# 15-OutputMultiplexing.net
KiCad netlist of a schematic drawn in Altium Designer
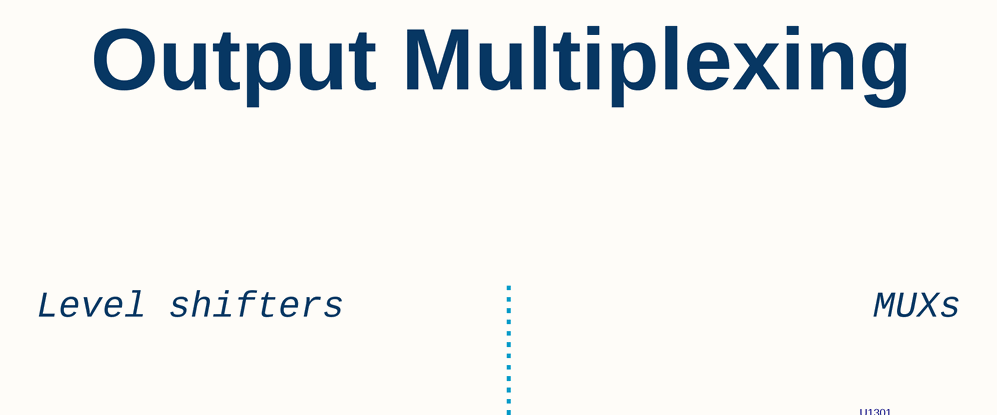
[diagram p0: 15-OutputMultiplexing.SchDoc, top left]
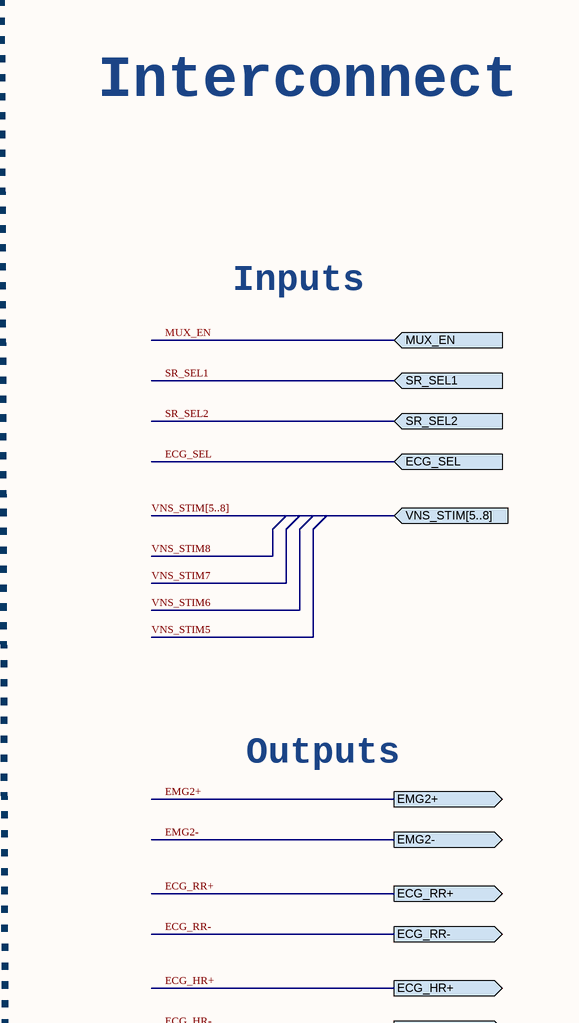
[diagram p1: 15-OutputMultiplexing.SchDoc, top right]
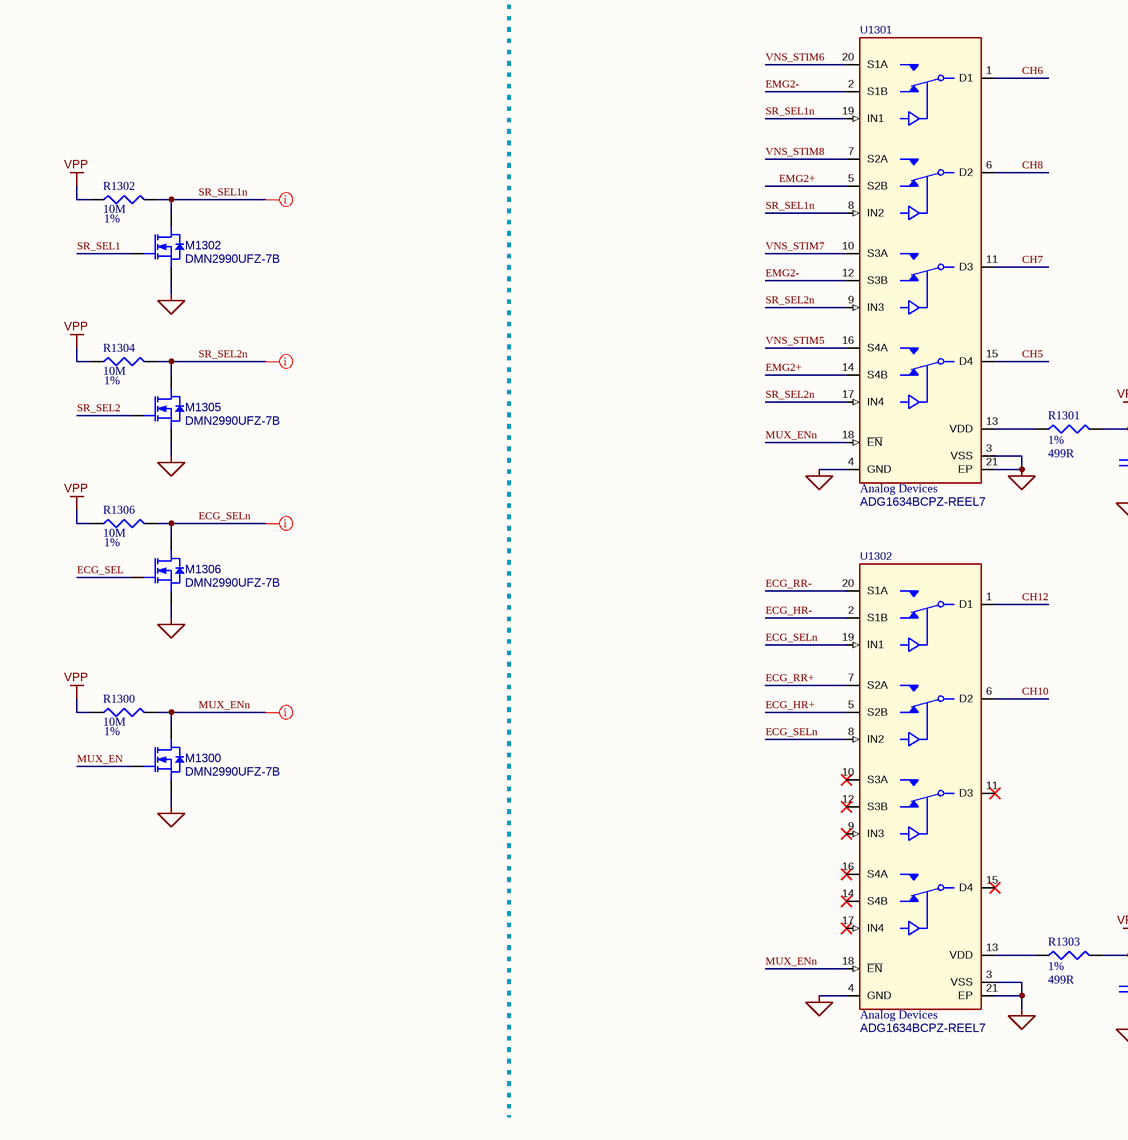
[diagram p2: 15-OutputMultiplexing.SchDoc, bottom left]
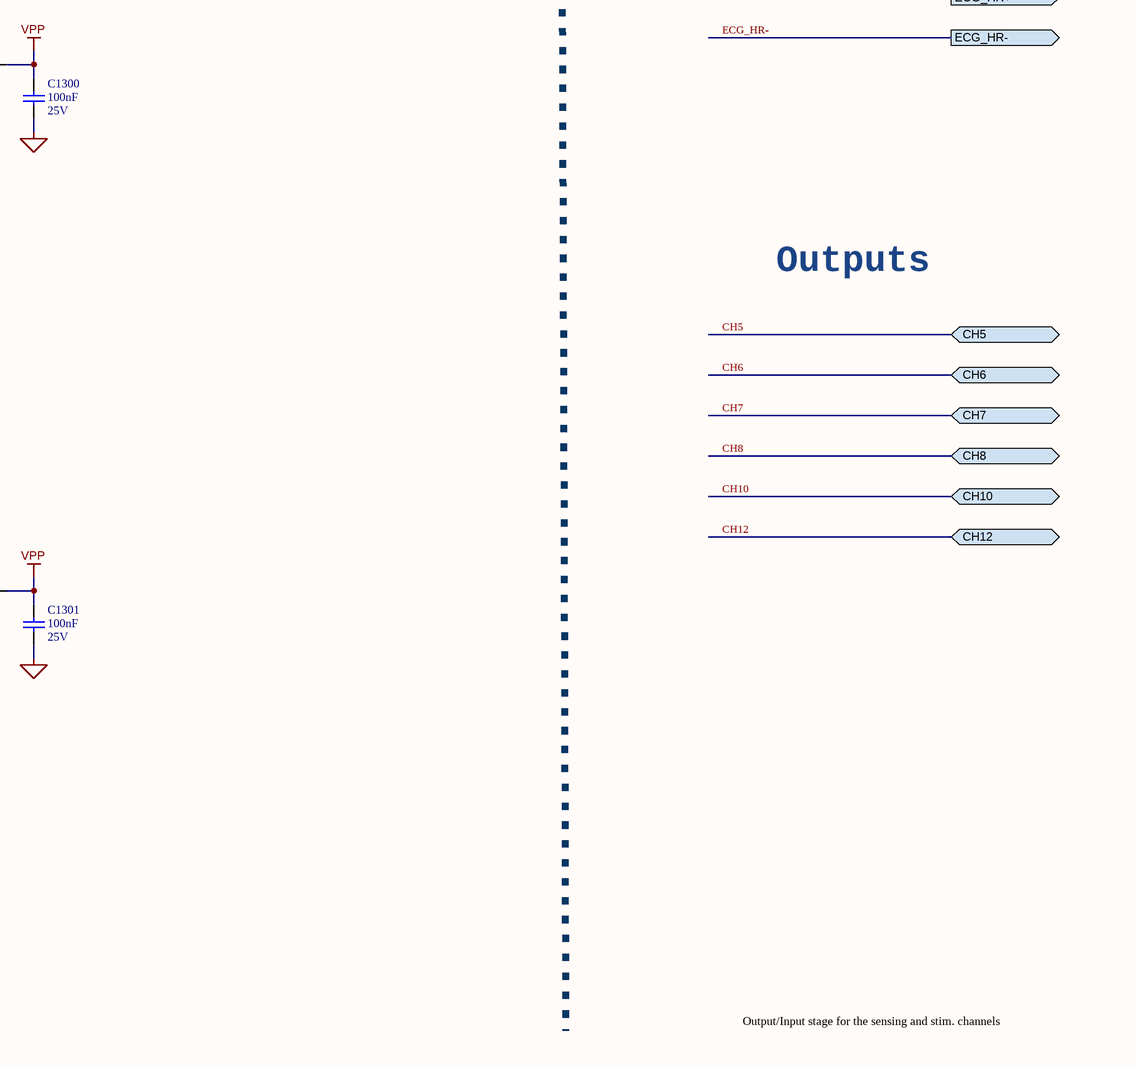
[diagram p3: 15-OutputMultiplexing.SchDoc, bottom right]

(export (version "E")
  (design (tool "Eeschema 10.0.6"))
  (components
    (comp (ref "C1300")
      (value "100nF")
      (footprint "C0201_C")
      (fields
        (field (name "MANUFACTURER") "Murata")
        (field (name "MANUFACTURER PART NUMBER") "GRM033R61E104KE14J")
        (field (name "RATED DC VOLTAGE (URDC)") "25V")
      )
      (libsource (lib "MP-LIBRARY") (part "GRM033R61E104KE14J"))
    )
    (comp (ref "C1301")
      (value "100nF")
      (footprint "C0201_C")
      (fields
        (field (name "MANUFACTURER") "Murata")
        (field (name "MANUFACTURER PART NUMBER") "GRM033R61E104KE14J")
        (field (name "RATED DC VOLTAGE (URDC)") "25V")
      )
      (libsource (lib "MP-LIBRARY") (part "GRM033R61E104KE14J"))
    )
    (comp (ref "M1300")
      (value "DMN2990UFZ-7B")
      (footprint "DIODESINC_X2-DFN0606-3")
      (description "MOSFET, N-Chan, 20V, 170mA, DFN0606")
      (fields (field (name "MANUFACTURER") "Diodes Inc"))
      (libsource (lib "MP-LIBRARY") (part "DMN2990UFZ-7B"))
    )
    (comp (ref "M1302")
      (value "DMN2990UFZ-7B")
      (footprint "DIODESINC_X2-DFN0606-3")
      (description "MOSFET, N-Chan, 20V, 170mA, DFN0606")
      (fields (field (name "MANUFACTURER") "Diodes Inc"))
      (libsource (lib "MP-LIBRARY") (part "DMN2990UFZ-7B"))
    )
    (comp (ref "M1305")
      (value "DMN2990UFZ-7B")
      (footprint "DIODESINC_X2-DFN0606-3")
      (description "MOSFET, N-Chan, 20V, 170mA, DFN0606")
      (fields (field (name "MANUFACTURER") "Diodes Inc"))
      (libsource (lib "MP-LIBRARY") (part "DMN2990UFZ-7B"))
    )
    (comp (ref "M1306")
      (value "DMN2990UFZ-7B")
      (footprint "DIODESINC_X2-DFN0606-3")
      (description "MOSFET, N-Chan, 20V, 170mA, DFN0606")
      (fields (field (name "MANUFACTURER") "Diodes Inc"))
      (libsource (lib "MP-LIBRARY") (part "DMN2990UFZ-7B"))
    )
    (comp (ref "R1300")
      (value "10M")
      (footprint "R0201_C")
      (fields
        (field (name "MANUFACTURER") "Vishay Draloric")
        (field (name "MANUFACTURER PART NUMBER") "CRCW020110M0FNED")
        (field (name "TOLERANCE") "1%")
        (field (name "POWER") "50mW")
      )
      (libsource (lib "MP-LIBRARY") (part "CRCW020110M0FNED"))
    )
    (comp (ref "R1301")
      (value "499R")
      (footprint "RES0402_REDUCED")
      (fields
        (field (name "MANUFACTURER") "Vishay Dale")
        (field (name "MANUFACTURER PART NUMBER") "CRCW0402499RFKEDHP")
        (field (name "POWER") "200mW")
        (field (name "TOLERANCE") "1%")
      )
      (libsource (lib "MP-LIBRARY") (part "CRCW0402499RFKEDHP"))
    )
    (comp (ref "R1302")
      (value "10M")
      (footprint "R0201_C")
      (fields
        (field (name "MANUFACTURER") "Vishay Draloric")
        (field (name "MANUFACTURER PART NUMBER") "CRCW020110M0FNED")
        (field (name "TOLERANCE") "1%")
        (field (name "POWER") "50mW")
      )
      (libsource (lib "MP-LIBRARY") (part "CRCW020110M0FNED"))
    )
    (comp (ref "R1303")
      (value "499R")
      (footprint "RES0402_REDUCED")
      (fields
        (field (name "MANUFACTURER") "Vishay Dale")
        (field (name "MANUFACTURER PART NUMBER") "CRCW0402499RFKEDHP")
        (field (name "POWER") "200mW")
        (field (name "TOLERANCE") "1%")
      )
      (libsource (lib "MP-LIBRARY") (part "CRCW0402499RFKEDHP"))
    )
    (comp (ref "R1304")
      (value "10M")
      (footprint "R0201_C")
      (fields
        (field (name "MANUFACTURER") "Vishay Draloric")
        (field (name "MANUFACTURER PART NUMBER") "CRCW020110M0FNED")
        (field (name "TOLERANCE") "1%")
        (field (name "POWER") "50mW")
      )
      (libsource (lib "MP-LIBRARY") (part "CRCW020110M0FNED"))
    )
    (comp (ref "R1306")
      (value "10M")
      (footprint "R0201_C")
      (fields
        (field (name "MANUFACTURER") "Vishay Draloric")
        (field (name "MANUFACTURER PART NUMBER") "CRCW020110M0FNED")
        (field (name "TOLERANCE") "1%")
        (field (name "POWER") "50mW")
      )
      (libsource (lib "MP-LIBRARY") (part "CRCW020110M0FNED"))
    )
    (comp (ref "U1301")
      (value "ADG1634BCPZ-REEL7")
      (footprint "AD_CP-20-10")
      (description "IC SWITCH SPDTX4 4.5OHM 20LFCSP")
      (fields (field (name "MANUFACTURER") "Analog Devices"))
      (libsource (lib "MP-LIBRARY") (part "ADG1634BCPZ-REEL7"))
    )
    (comp (ref "U1302")
      (value "ADG1634BCPZ-REEL7")
      (footprint "AD_CP-20-10")
      (description "IC SWITCH SPDTX4 4.5OHM 20LFCSP")
      (fields (field (name "MANUFACTURER") "Analog Devices"))
      (libsource (lib "MP-LIBRARY") (part "ADG1634BCPZ-REEL7"))
    )
  )
  (nets
    (net (code "1") (name "/CH5") (class "Default")
      (node (ref "U1301") (pin "15") (pinfunction "D4_15") (pintype "passive"))
    )
    (net (code "2") (name "/CH6") (class "Default")
      (node (ref "U1301") (pin "1") (pinfunction "D1_1") (pintype "passive"))
    )
    (net (code "3") (name "/CH7") (class "Default")
      (node (ref "U1301") (pin "11") (pinfunction "D3_11") (pintype "passive"))
    )
    (net (code "4") (name "/CH8") (class "Default")
      (node (ref "U1301") (pin "6") (pinfunction "D2_6") (pintype "passive"))
    )
    (net (code "5") (name "/CH10") (class "Default")
      (node (ref "U1302") (pin "6") (pinfunction "D2_6") (pintype "passive"))
    )
    (net (code "6") (name "/CH12") (class "Default")
      (node (ref "U1302") (pin "1") (pinfunction "D1_1") (pintype "passive"))
    )
    (net (code "7") (name "/ECG_HR+") (class "Default")
      (node (ref "U1302") (pin "5") (pinfunction "S2B_5") (pintype "passive"))
    )
    (net (code "8") (name "/ECG_HR-") (class "Default")
      (node (ref "U1302") (pin "2") (pinfunction "S1B_2") (pintype "passive"))
    )
    (net (code "9") (name "/ECG_RR+") (class "Default")
      (node (ref "U1302") (pin "7") (pinfunction "S2A_7") (pintype "passive"))
    )
    (net (code "10") (name "/ECG_RR-") (class "Default")
      (node (ref "U1302") (pin "20") (pinfunction "S1A_20") (pintype "passive"))
    )
    (net (code "11") (name "/ECG_SEL") (class "Default")
      (node (ref "M1306") (pin "1") (pinfunction "G_1") (pintype "passive"))
    )
    (net (code "12") (name "/ECG_SELn") (class "Default")
      (node (ref "M1306") (pin "3") (pinfunction "D_3") (pintype "passive"))
      (node (ref "R1306") (pin "2") (pinfunction "2_2") (pintype "passive"))
      (node (ref "U1302") (pin "19") (pinfunction "IN1_19") (pintype "input"))
      (node (ref "U1302") (pin "8") (pinfunction "IN2_8") (pintype "input"))
    )
    (net (code "13") (name "/EMG2+") (class "Default")
      (node (ref "U1301") (pin "14") (pinfunction "S4B_14") (pintype "passive"))
      (node (ref "U1301") (pin "5") (pinfunction "S2B_5") (pintype "passive"))
    )
    (net (code "14") (name "/EMG2-") (class "Default")
      (node (ref "U1301") (pin "12") (pinfunction "S3B_12") (pintype "passive"))
      (node (ref "U1301") (pin "2") (pinfunction "S1B_2") (pintype "passive"))
    )
    (net (code "15") (name "/MUX_EN") (class "Default")
      (node (ref "M1300") (pin "1") (pinfunction "G_1") (pintype "passive"))
    )
    (net (code "16") (name "/MUX_ENn") (class "Default")
      (node (ref "M1300") (pin "3") (pinfunction "D_3") (pintype "passive"))
      (node (ref "R1300") (pin "2") (pinfunction "2_2") (pintype "passive"))
      (node (ref "U1301") (pin "18") (pinfunction "~{EN}_18") (pintype "input"))
      (node (ref "U1302") (pin "18") (pinfunction "~{EN}_18") (pintype "input"))
    )
    (net (code "17") (name "/SR_SEL1") (class "Default")
      (node (ref "M1302") (pin "1") (pinfunction "G_1") (pintype "passive"))
    )
    (net (code "18") (name "/SR_SEL1n") (class "Default")
      (node (ref "M1302") (pin "3") (pinfunction "D_3") (pintype "passive"))
      (node (ref "R1302") (pin "2") (pinfunction "2_2") (pintype "passive"))
      (node (ref "U1301") (pin "19") (pinfunction "IN1_19") (pintype "input"))
      (node (ref "U1301") (pin "8") (pinfunction "IN2_8") (pintype "input"))
    )
    (net (code "19") (name "/SR_SEL2") (class "Default")
      (node (ref "M1305") (pin "1") (pinfunction "G_1") (pintype "passive"))
    )
    (net (code "20") (name "/SR_SEL2n") (class "Default")
      (node (ref "M1305") (pin "3") (pinfunction "D_3") (pintype "passive"))
      (node (ref "R1304") (pin "2") (pinfunction "2_2") (pintype "passive"))
      (node (ref "U1301") (pin "17") (pinfunction "IN4_17") (pintype "input"))
      (node (ref "U1301") (pin "9") (pinfunction "IN3_9") (pintype "input"))
    )
    (net (code "21") (name "/VNS_STIM5") (class "Default")
      (node (ref "U1301") (pin "16") (pinfunction "S4A_16") (pintype "passive"))
    )
    (net (code "22") (name "/VNS_STIM6") (class "Default")
      (node (ref "U1301") (pin "20") (pinfunction "S1A_20") (pintype "passive"))
    )
    (net (code "23") (name "/VNS_STIM7") (class "Default")
      (node (ref "U1301") (pin "10") (pinfunction "S3A_10") (pintype "passive"))
    )
    (net (code "24") (name "/VNS_STIM8") (class "Default")
      (node (ref "U1301") (pin "7") (pinfunction "S2A_7") (pintype "passive"))
    )
    (net (code "26") (name "GND") (class "Default")
      (node (ref "C1300") (pin "1") (pinfunction "1_1") (pintype "passive"))
      (node (ref "C1301") (pin "1") (pinfunction "1_1") (pintype "passive"))
      (node (ref "M1300") (pin "2") (pinfunction "S_2") (pintype "passive"))
      (node (ref "M1302") (pin "2") (pinfunction "S_2") (pintype "passive"))
      (node (ref "M1305") (pin "2") (pinfunction "S_2") (pintype "passive"))
      (node (ref "M1306") (pin "2") (pinfunction "S_2") (pintype "passive"))
      (node (ref "U1301") (pin "21") (pinfunction "EP_21") (pintype "power_in"))
      (node (ref "U1301") (pin "3") (pinfunction "VSS_3") (pintype "power_in"))
      (node (ref "U1301") (pin "4") (pinfunction "GND_4") (pintype "power_in"))
      (node (ref "U1302") (pin "21") (pinfunction "EP_21") (pintype "power_in"))
      (node (ref "U1302") (pin "3") (pinfunction "VSS_3") (pintype "power_in"))
      (node (ref "U1302") (pin "4") (pinfunction "GND_4") (pintype "power_in"))
    )
    (net (code "27") (name "Net-(U1301-VDD)") (class "Default")
      (node (ref "R1301") (pin "1") (pinfunction "1_1") (pintype "passive"))
      (node (ref "U1301") (pin "13") (pinfunction "VDD_13") (pintype "power_in"))
    )
    (net (code "28") (name "Net-(U1302-VDD)") (class "Default")
      (node (ref "R1303") (pin "1") (pinfunction "1_1") (pintype "passive"))
      (node (ref "U1302") (pin "13") (pinfunction "VDD_13") (pintype "power_in"))
    )
    (net (code "29") (name "VPP") (class "Default")
      (node (ref "C1300") (pin "2") (pinfunction "2_2") (pintype "passive"))
      (node (ref "C1301") (pin "2") (pinfunction "2_2") (pintype "passive"))
      (node (ref "R1300") (pin "1") (pinfunction "1_1") (pintype "passive"))
      (node (ref "R1301") (pin "2") (pinfunction "2_2") (pintype "passive"))
      (node (ref "R1302") (pin "1") (pinfunction "1_1") (pintype "passive"))
      (node (ref "R1303") (pin "2") (pinfunction "2_2") (pintype "passive"))
      (node (ref "R1304") (pin "1") (pinfunction "1_1") (pintype "passive"))
      (node (ref "R1306") (pin "1") (pinfunction "1_1") (pintype "passive"))
    )
    (net (code "30") (name "unconnected-(U1302-D3-Pad11)") (class "Default")
      (node (ref "U1302") (pin "11") (pinfunction "D3_11") (pintype "passive+no_connect"))
    )
    (net (code "31") (name "unconnected-(U1302-D4-Pad15)") (class "Default")
      (node (ref "U1302") (pin "15") (pinfunction "D4_15") (pintype "passive+no_connect"))
    )
    (net (code "32") (name "unconnected-(U1302-IN3-Pad9)") (class "Default")
      (node (ref "U1302") (pin "9") (pinfunction "IN3_9") (pintype "input+no_connect"))
    )
    (net (code "33") (name "unconnected-(U1302-IN4-Pad17)") (class "Default")
      (node (ref "U1302") (pin "17") (pinfunction "IN4_17") (pintype "input+no_connect"))
    )
    (net (code "34") (name "unconnected-(U1302-S3A-Pad10)") (class "Default")
      (node (ref "U1302") (pin "10") (pinfunction "S3A_10") (pintype "passive+no_connect"))
    )
    (net (code "35") (name "unconnected-(U1302-S3B-Pad12)") (class "Default")
      (node (ref "U1302") (pin "12") (pinfunction "S3B_12") (pintype "passive+no_connect"))
    )
    (net (code "36") (name "unconnected-(U1302-S4A-Pad16)") (class "Default")
      (node (ref "U1302") (pin "16") (pinfunction "S4A_16") (pintype "passive+no_connect"))
    )
    (net (code "37") (name "unconnected-(U1302-S4B-Pad14)") (class "Default")
      (node (ref "U1302") (pin "14") (pinfunction "S4B_14") (pintype "passive+no_connect"))
    )
  )
)
